# ProProject_ONGEKI.net
KiCad netlist of a schematic drawn in EasyEDA Pro
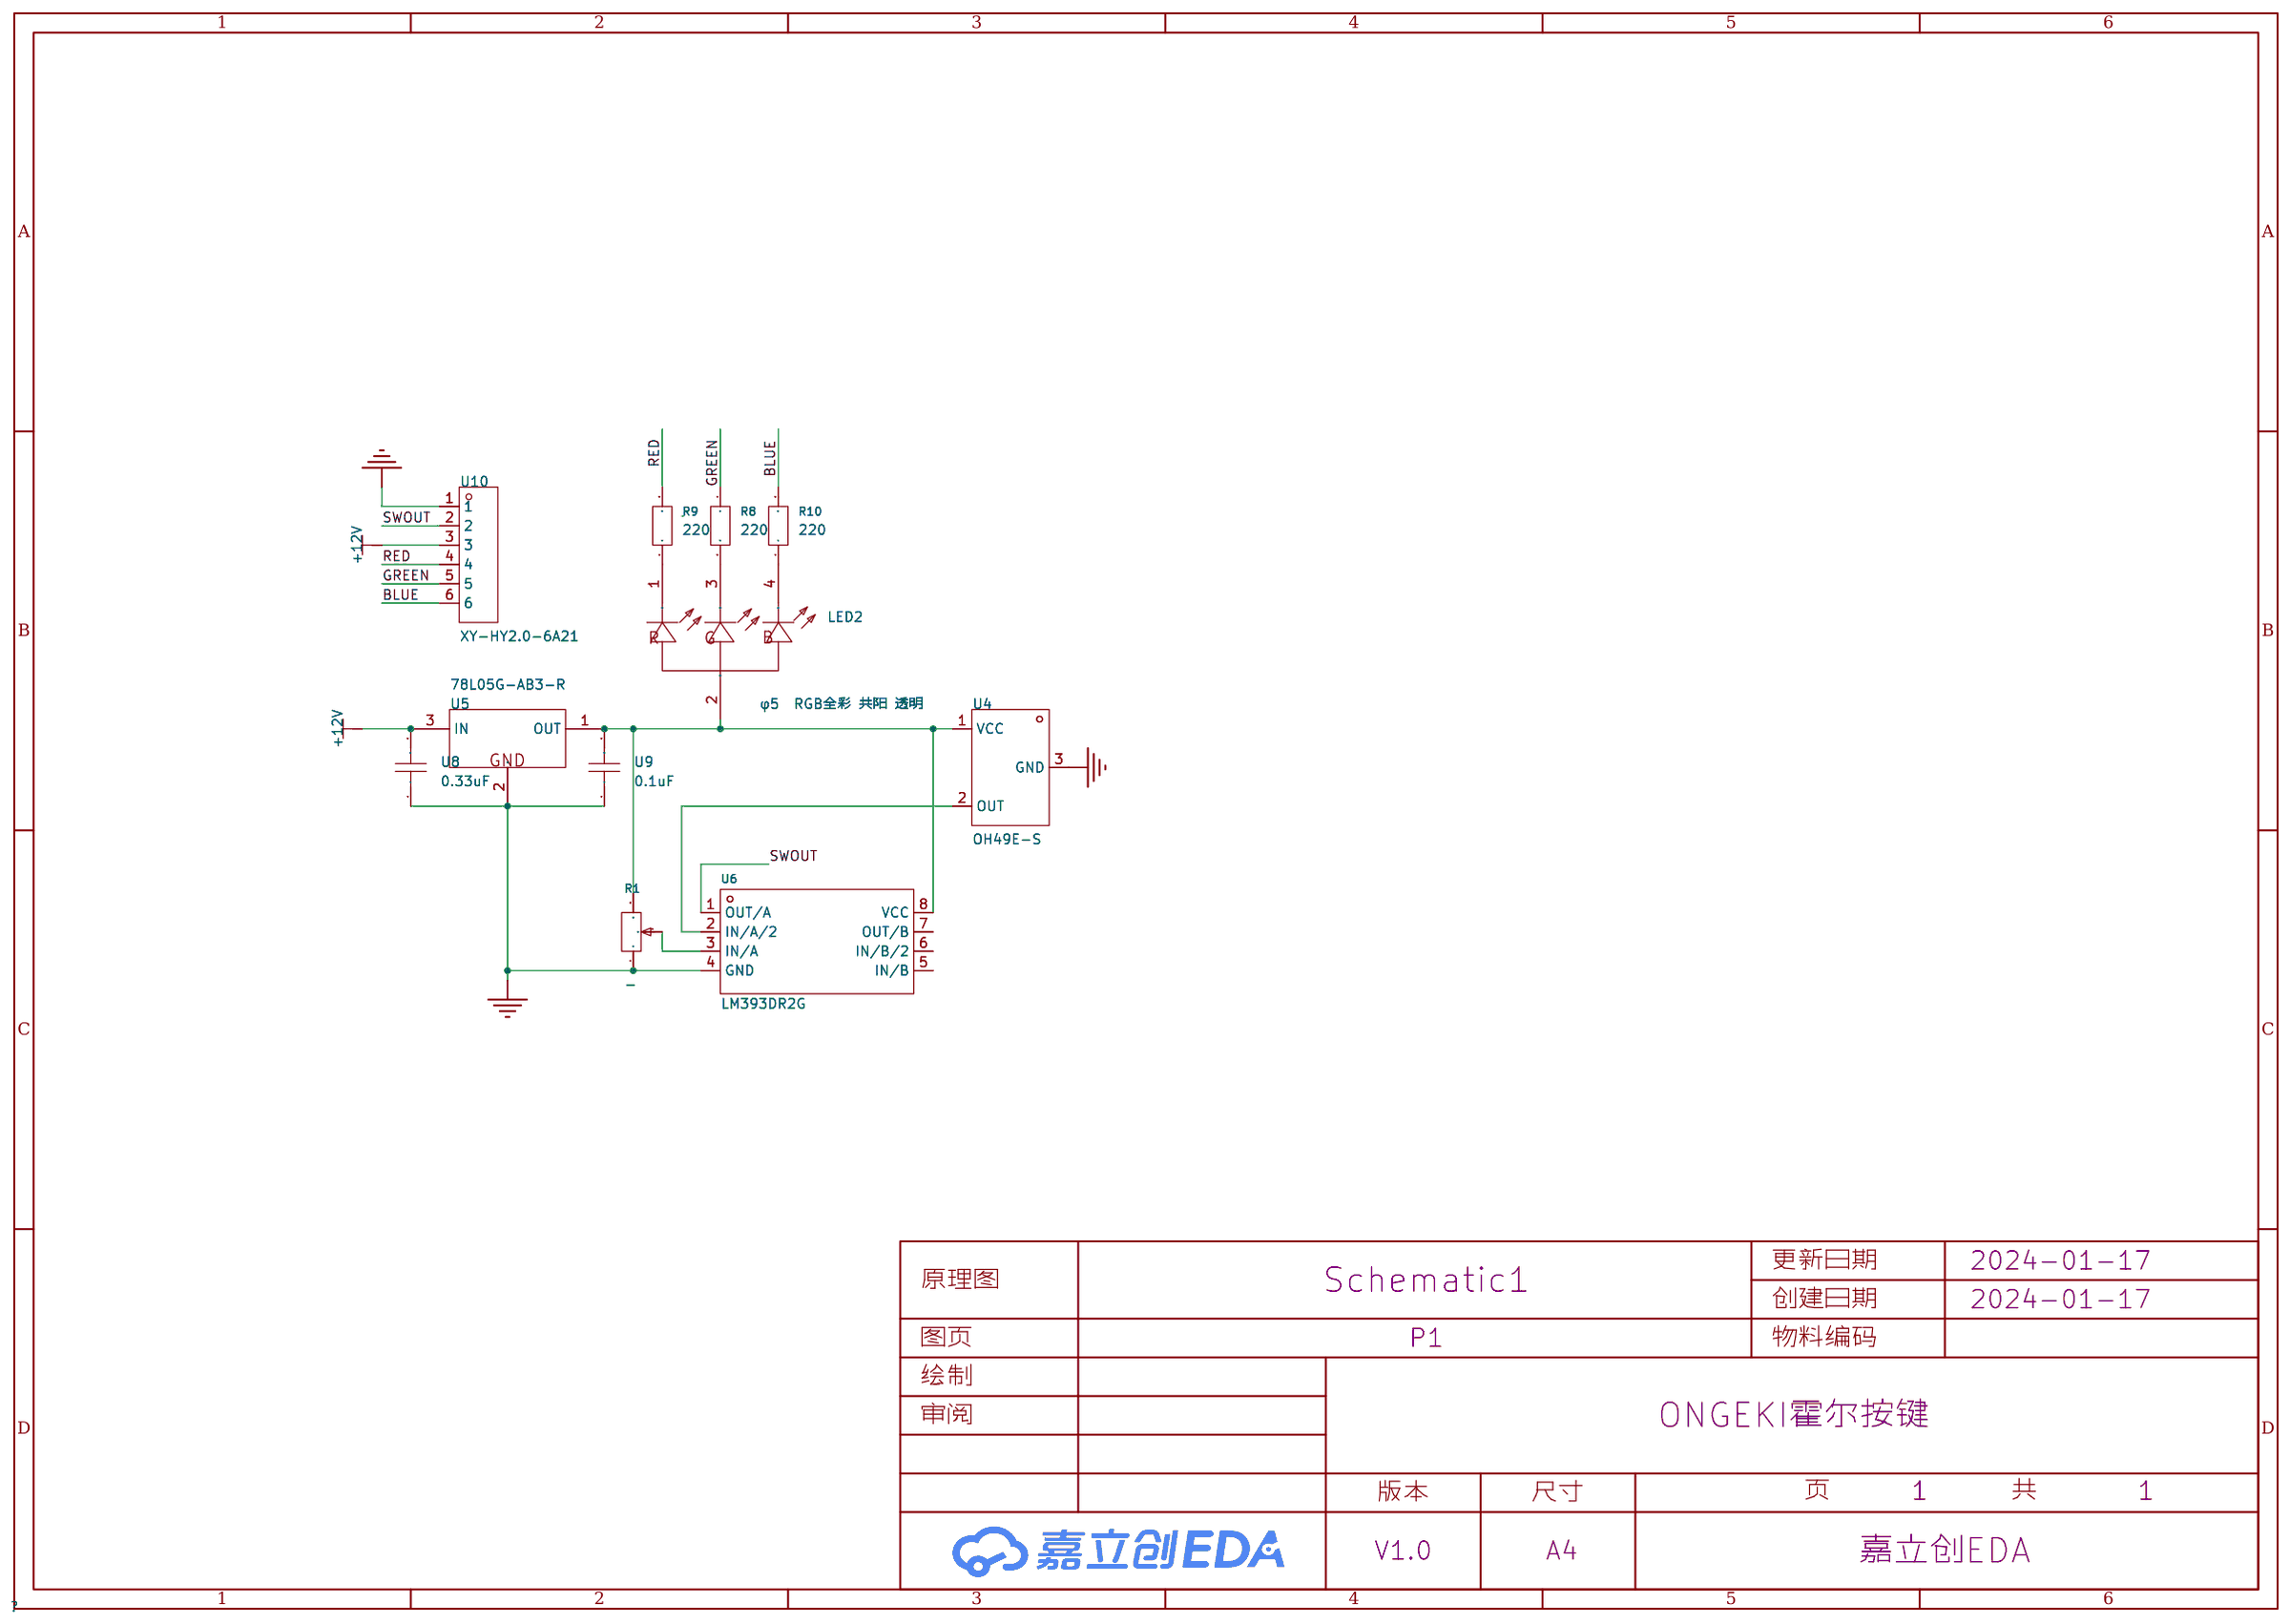
[diagram p0: schematic sheet]

(export (version "E")
  (design (tool "Eeschema 10.0.6"))
  (components
    (comp (ref "LED2")
      (value "φ5  RGB全彩 共阳 透明")
      (footprint "easyedapro:LED-TH_4P-BD5.8-P1.30")
      (description "主波长/色坐标:620~625nm红,515~520nm绿,460~465nm蓝;照明颜色:RGB三色;")
      (libsource (lib "easyedapro") (part "φ5 RGB Transparent"))
    )
    (comp (ref "R1")
      (value "-")
      (footprint "easyedapro:RES-ADJ-TH_3P-L9.5-W4.85-P2.50-BL-BS")
      (description "阻值:-;功率:-;")
      (fields (field (name "Manufacturer Part") "3296W-1-105"))
      (libsource (lib "easyedapro") (part "3296W-1-105"))
    )
    (comp (ref "R8")
      (value "220")
      (footprint "easyedapro:R0603")
      (description "阻值:1kΩ;精度:±1%;")
      (fields (field (name "Manufacturer Part") "SCR0603F1K") (field (name "Manufacturer") "VO(翔胜)"))
      (libsource (lib "easyedapro") (part "SCR0603F1K"))
    )
    (comp (ref "R9")
      (value "220")
      (footprint "easyedapro:R0603")
      (description "阻值:1kΩ;精度:±1%;")
      (fields (field (name "Manufacturer Part") "SCR0603F1K") (field (name "Manufacturer") "VO(翔胜)"))
      (libsource (lib "easyedapro") (part "SCR0603F1K"))
    )
    (comp (ref "R10")
      (value "220")
      (footprint "easyedapro:R0603")
      (description "阻值:1kΩ;精度:±1%;")
      (fields (field (name "Manufacturer Part") "SCR0603F1K") (field (name "Manufacturer") "VO(翔胜)"))
      (libsource (lib "easyedapro") (part "SCR0603F1K"))
    )
    (comp (ref "U4")
      (value "OH49E-S")
      (footprint "easyedapro:SOT-23-3_L2.9-W1.6-P1.90-LS2.8-BR")
      (fields (field (name "Manufacturer") "南京欧卓"))
      (libsource (lib "easyedapro") (part "OH49E-S"))
    )
    (comp (ref "U5")
      (value "78L05G-AB3-R")
      (footprint "easyedapro:SOT-89-3_L4.5-W2.5-P1.50-LS4.2-BR")
      (description "输出类型:固定;输出极性:正;输出通道数:1;最大输入电压:30V;输出电压:5V;压差:1.7V@(40mA);输出电流:100mA;")
      (fields (field (name "Manufacturer") "UTC(友顺)"))
      (libsource (lib "easyedapro") (part "78L05G-AB3-R"))
    )
    (comp (ref "U6")
      (value "LM393DR2G")
      (footprint "easyedapro:SOIC-8_L5.0-W4.0-P1.27-LS6.0-BL")
      (description "比较器组数:2;输入失调电压(Vos):5mV;输入偏置电流(Ib):250nA;")
      (fields (field (name "Manufacturer") "onsemi(安森美)"))
      (libsource (lib "easyedapro") (part "LM393DR2G"))
    )
    (comp (ref "U8")
      (value "0.33uF")
      (footprint "easyedapro:C0805")
      (description "容值:30pF;精度:±20%;额定电压:16V;材质(温度系数):X8R;")
      (fields
        (field (name "Manufacturer Part") "C0805X300M4HAC7800")
        (field (name "Manufacturer") "KEMET(基美)")
      )
      (libsource (lib "easyedapro") (part "C0805X300M4HAC7800"))
    )
    (comp (ref "U9")
      (value "0.1uF")
      (footprint "easyedapro:C0805")
      (description "容值:30pF;精度:±20%;额定电压:16V;材质(温度系数):X8R;")
      (fields
        (field (name "Manufacturer Part") "C0805X300M4HAC7800")
        (field (name "Manufacturer") "KEMET(基美)")
      )
      (libsource (lib "easyedapro") (part "C0805X300M4HAC7800"))
    )
    (comp (ref "U10")
      (value "XY-HY2.0-6A21")
      (footprint "easyedapro:HDR-TH_6P-P2.00-H-F")
      (description "插针结构:1x6P;间距:2mm;安装方式:弯插;总PIN数:6P;排数:1;每排PIN数:6;行距:2mm;额定电流:2A;工作温度范围:-25°C~+85°C;")
      (fields (field (name "Manufacturer") "XYECONN(辛译)"))
      (libsource (lib "easyedapro") (part "XY-HY2.0-6A21"))
    )
  )
  (nets
    (net (code "1") (name "+12V") (class "Default")
      (node (ref "U10") (pin "3") (pinfunction "3_3") (pintype "unspecified"))
      (node (ref "U5") (pin "3") (pinfunction "IN_3") (pintype "input"))
      (node (ref "U8") (pin "2") (pinfunction "2_2") (pintype "input"))
    )
    (net (code "2") (name "/BLUE") (class "Default")
      (node (ref "R10") (pin "2") (pinfunction "2_2") (pintype "input"))
      (node (ref "U10") (pin "6") (pinfunction "6_6") (pintype "unspecified"))
    )
    (net (code "3") (name "/GREEN") (class "Default")
      (node (ref "R8") (pin "1") (pinfunction "1_1") (pintype "input"))
      (node (ref "U10") (pin "5") (pinfunction "5_5") (pintype "unspecified"))
    )
    (net (code "4") (name "/RED") (class "Default")
      (node (ref "R9") (pin "2") (pinfunction "2_2") (pintype "input"))
      (node (ref "U10") (pin "4") (pinfunction "4_4") (pintype "unspecified"))
    )
    (net (code "5") (name "/SWOUT") (class "Default")
      (node (ref "U10") (pin "2") (pinfunction "2_2") (pintype "unspecified"))
      (node (ref "U6") (pin "1") (pinfunction "OUT/A_1") (pintype "input"))
    )
    (net (code "6") (name "GND") (class "Default")
      (node (ref "R1") (pin "1") (pinfunction "1_1") (pintype "input"))
      (node (ref "U10") (pin "1") (pinfunction "1_1") (pintype "unspecified"))
      (node (ref "U4") (pin "3") (pinfunction "GND_3") (pintype "input"))
      (node (ref "U5") (pin "2") (pinfunction "GND_2") (pintype "input"))
      (node (ref "U6") (pin "4") (pinfunction "GND_4") (pintype "input"))
      (node (ref "U8") (pin "1") (pinfunction "1_1") (pintype "input"))
      (node (ref "U9") (pin "1") (pinfunction "1_1") (pintype "input"))
    )
    (net (code "7") (name "Net-(LED2-CA)") (class "Default")
      (node (ref "LED2") (pin "2") (pinfunction "CA_2") (pintype "input"))
      (node (ref "R1") (pin "3") (pinfunction "3_3") (pintype "input"))
      (node (ref "U4") (pin "1") (pinfunction "VCC_1") (pintype "input"))
      (node (ref "U5") (pin "1") (pinfunction "OUT_1") (pintype "input"))
      (node (ref "U6") (pin "8") (pinfunction "VCC_8") (pintype "input"))
      (node (ref "U9") (pin "2") (pinfunction "2_2") (pintype "input"))
    )
    (net (code "8") (name "Net-(LED2-KB)") (class "Default")
      (node (ref "LED2") (pin "4") (pinfunction "KB_4") (pintype "input"))
      (node (ref "R10") (pin "1") (pinfunction "1_1") (pintype "input"))
    )
    (net (code "9") (name "Net-(LED2-KG)") (class "Default")
      (node (ref "LED2") (pin "3") (pinfunction "KG_3") (pintype "input"))
      (node (ref "R8") (pin "2") (pinfunction "2_2") (pintype "input"))
    )
    (net (code "10") (name "Net-(LED2-KR)") (class "Default")
      (node (ref "LED2") (pin "1") (pinfunction "KR_1") (pintype "input"))
      (node (ref "R9") (pin "1") (pinfunction "1_1") (pintype "input"))
    )
    (net (code "11") (name "Net-(U4-OUT)") (class "Default")
      (node (ref "U4") (pin "2") (pinfunction "OUT_2") (pintype "input"))
      (node (ref "U6") (pin "2") (pinfunction "IN/A/2_2") (pintype "input"))
    )
    (net (code "12") (name "Net-(U6-IN{slash}A)") (class "Default")
      (node (ref "R1") (pin "2") (pinfunction "2_2") (pintype "input"))
      (node (ref "U6") (pin "3") (pinfunction "IN/A_3") (pintype "input"))
    )
    (net (code "13") (name "unconnected-(U6-IN{slash}B-Pad5)") (class "Default")
      (node (ref "U6") (pin "5") (pinfunction "IN/B_5") (pintype "input"))
    )
    (net (code "14") (name "unconnected-(U6-IN{slash}B{slash}2-Pad6)") (class "Default")
      (node (ref "U6") (pin "6") (pinfunction "IN/B/2_6") (pintype "input"))
    )
    (net (code "15") (name "unconnected-(U6-OUT{slash}B-Pad7)") (class "Default")
      (node (ref "U6") (pin "7") (pinfunction "OUT/B_7") (pintype "input"))
    )
  )
)
